# Pg6-Power_supply_1.net
KiCad netlist of a schematic drawn in Altium Designer
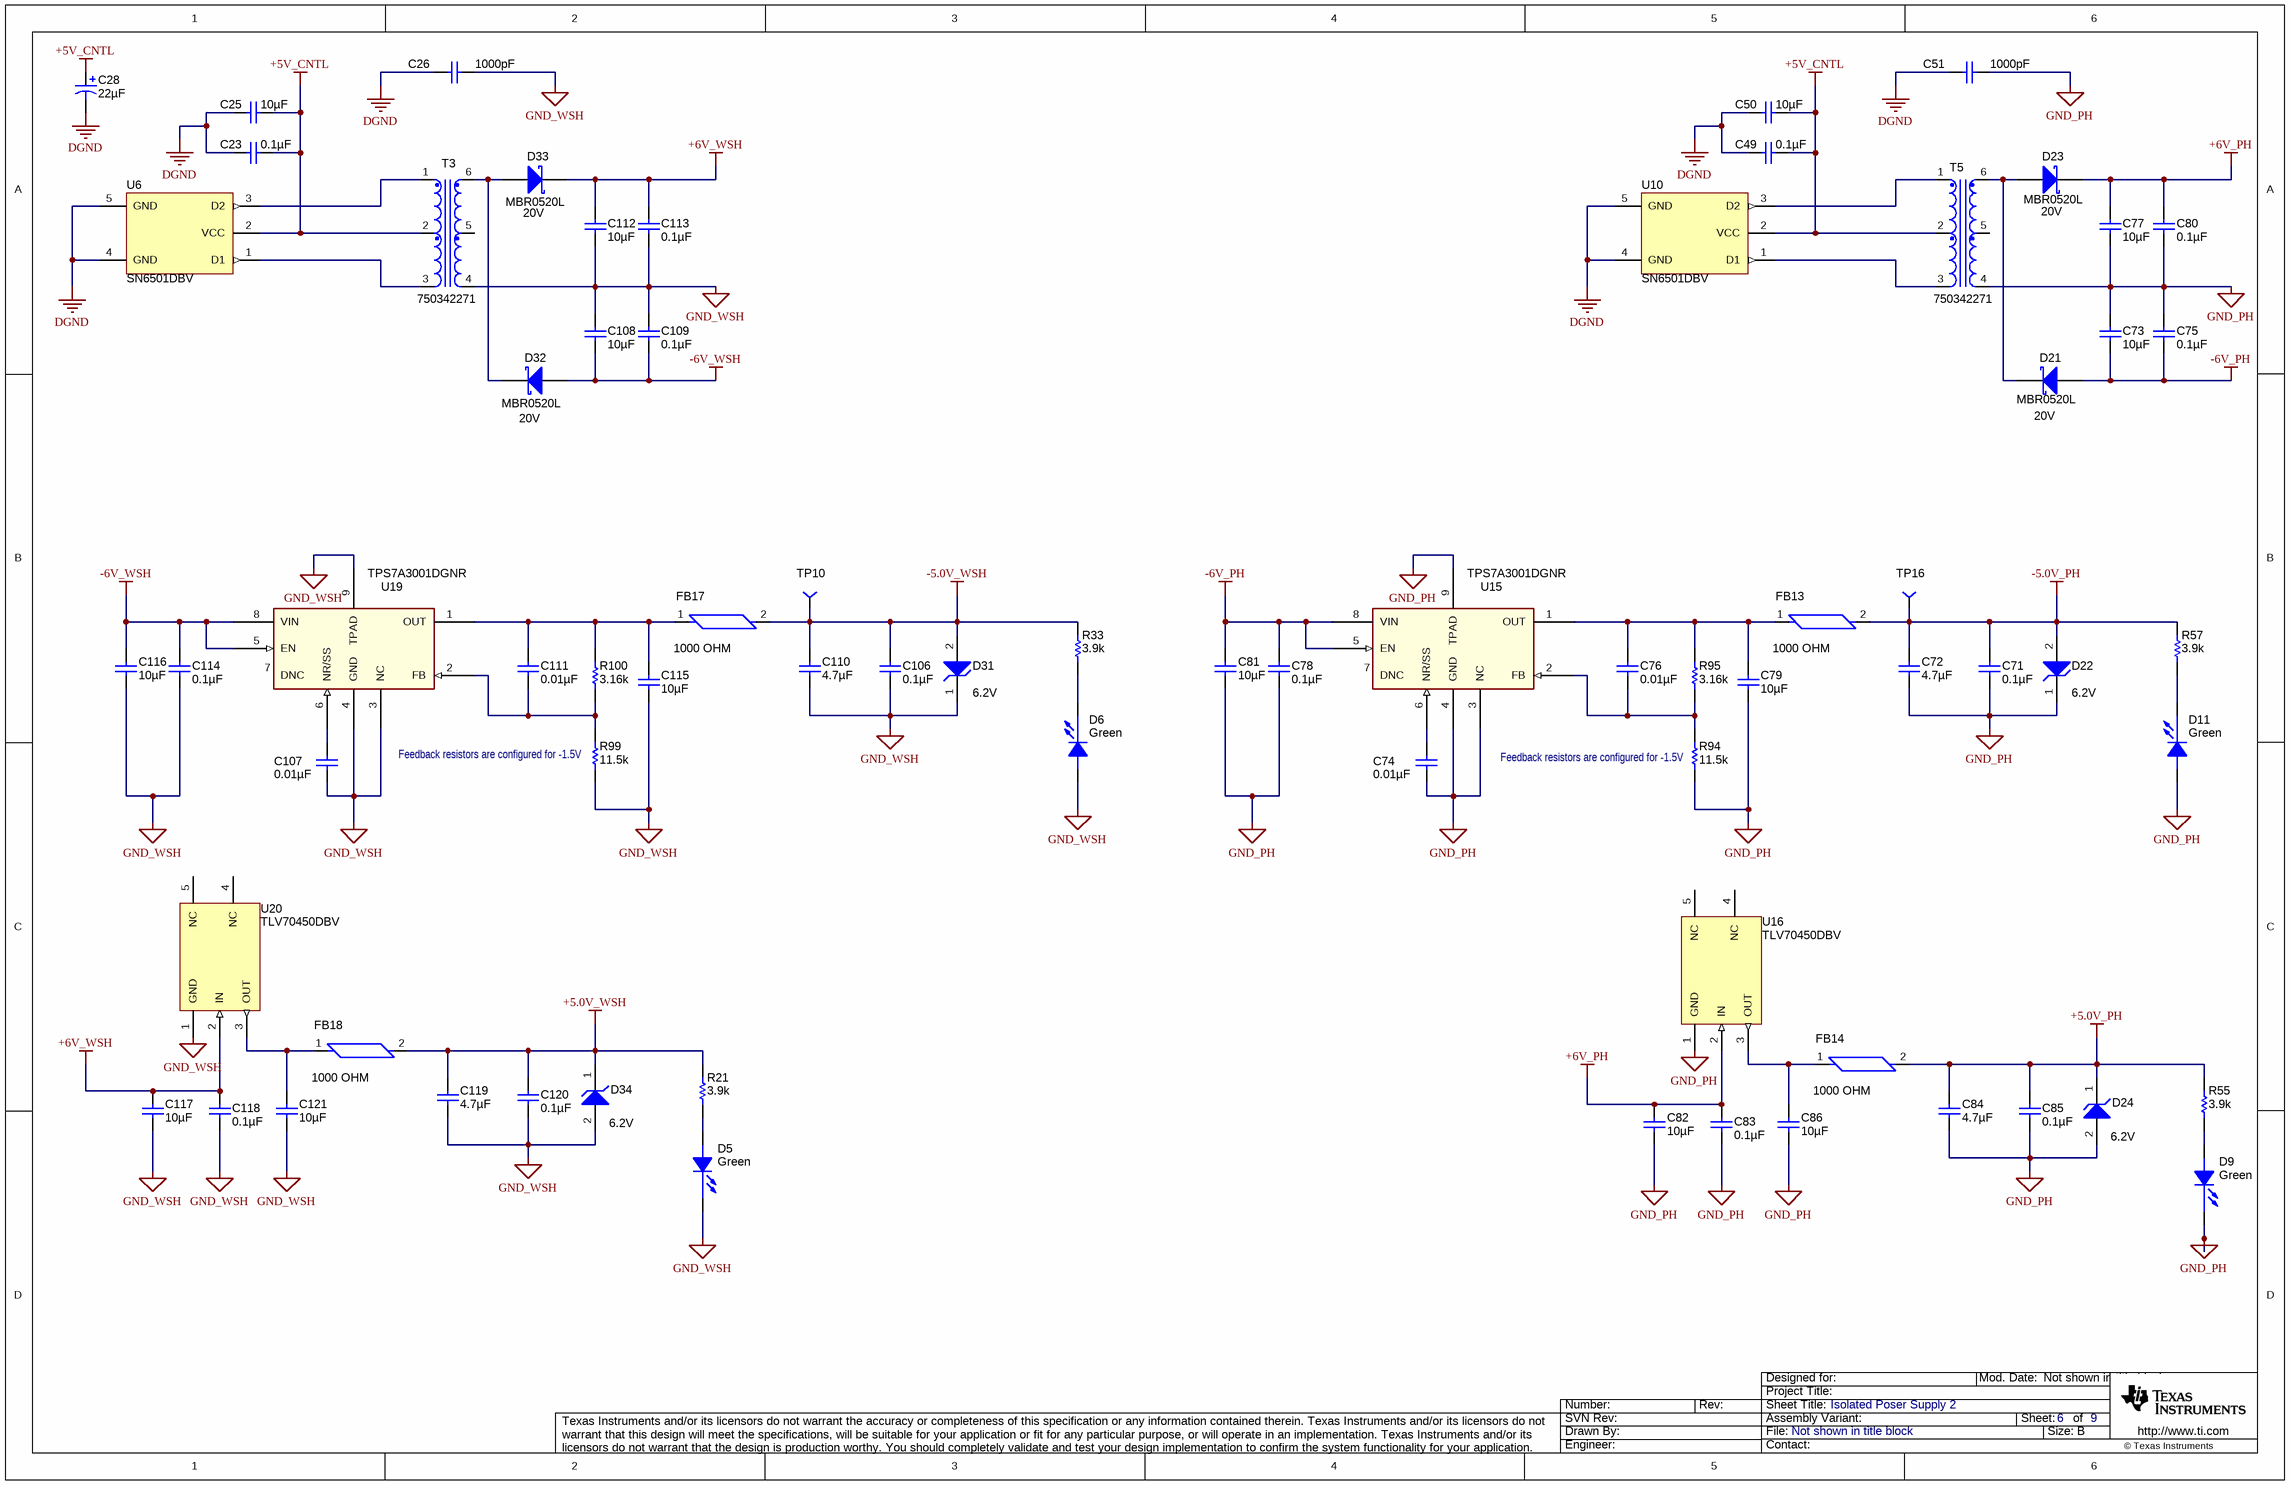
[diagram p0: Pg6-Power supply 1.SchDoc]

(export (version "E")
  (design (tool "Eeschema 10.0.6"))
  (components
    (comp (ref "C23")
      (value "~")
      (footprint "0603")
      (description "CAP, CERM, 0.1uF, 50V, +/-10%, X7R, 0603")
      (fields
        (field (name "PARTNUMBER") "C0603C104K5RACTU")
        (field (name "VALUEDISPLAYED") "0.1µF")
        (field (name "MANUFACTURER") "Kemet")
        (field (name "PUBLISHER") "Texas Instruments")
      )
      (libsource (lib "Capacitor_Ceramic") (part "C0603C104K5RACTU"))
    )
    (comp (ref "C25")
      (value "~")
      (footprint "1210")
      (description "CAP, CERM, 10uF, 35V, +/-20%, X7R, 1210")
      (fields
        (field (name "PARTNUMBER") "GMK325AB7106MM-T")
        (field (name "VALUEDISPLAYED") "10µF")
        (field (name "MANUFACTURER") "Taiyo Yuden")
        (field (name "PUBLISHER") "Texas Instruments")
      )
      (libsource (lib "Capacitor_Ceramic") (part "GMK325AB7106MM-T"))
    )
    (comp (ref "C26")
      (value "1000pF")
      (footprint "CAP_200mil")
      (description "CAP CER 1000PF 1KV 10% RADIAL")
      (fields
        (field (name "PARTNUMBER") "S102K29Y5PN63J5R")
        (field (name "MANUFACTURER") "Vishay BC Components")
        (field (name "PUBLISHER") "Texas Instruments")
      )
      (libsource (lib "TI-INDIA-ALTIUM") (part "202R18W102KV4E"))
    )
    (comp (ref "C28")
      (value "UUD1E220MCL1GS")
      (footprint "SM_RADIAL_5MM")
      (description "CAP, AL, 22uF, 25V, +/-20%, 0.76 ohm, SMD")
      (fields
        (field (name "VALUEDISPLAYED") "22µF")
        (field (name "MANUFACTURER") "Nichicon")
        (field (name "PUBLISHER") "Texas Instruments")
      )
      (libsource (lib "Capacitor_Aluminum") (part "UUD1E220MCL1GS"))
    )
    (comp (ref "C49")
      (value "~")
      (footprint "0603")
      (description "CAP, CERM, 0.1uF, 50V, +/-10%, X7R, 0603")
      (fields
        (field (name "PARTNUMBER") "C0603C104K5RACTU")
        (field (name "VALUEDISPLAYED") "0.1µF")
        (field (name "MANUFACTURER") "Kemet")
        (field (name "PUBLISHER") "Texas Instruments")
      )
      (libsource (lib "Capacitor_Ceramic") (part "C0603C104K5RACTU"))
    )
    (comp (ref "C50")
      (value "~")
      (footprint "1210")
      (description "CAP, CERM, 10uF, 35V, +/-20%, X7R, 1210")
      (fields
        (field (name "PARTNUMBER") "GMK325AB7106MM-T")
        (field (name "VALUEDISPLAYED") "10µF")
        (field (name "MANUFACTURER") "Taiyo Yuden")
        (field (name "PUBLISHER") "Texas Instruments")
      )
      (libsource (lib "Capacitor_Ceramic") (part "GMK325AB7106MM-T"))
    )
    (comp (ref "C51")
      (value "1000pF")
      (footprint "CAP_200mil")
      (description "CAP CER 1000PF 1KV 10% RADIAL")
      (fields
        (field (name "PARTNUMBER") "S102K29Y5PN63J5R")
        (field (name "MANUFACTURER") "Vishay BC Components")
        (field (name "PUBLISHER") "Texas Instruments")
      )
      (libsource (lib "TI-INDIA-ALTIUM") (part "202R18W102KV4E"))
    )
    (comp (ref "C71")
      (value "~")
      (footprint "0603")
      (description "CAP, CERM, 0.1uF, 50V, +/-10%, X7R, 0603")
      (fields
        (field (name "PARTNUMBER") "C0603C104K5RACTU")
        (field (name "VALUEDISPLAYED") "0.1µF")
        (field (name "MANUFACTURER") "Kemet")
        (field (name "PUBLISHER") "Texas Instruments")
      )
      (libsource (lib "Capacitor_Ceramic") (part "C0603C104K5RACTU"))
    )
    (comp (ref "C72")
      (value "~")
      (footprint "0805_HV")
      (description "CAP, CERM, 4.7uF, 50V, +/-10%, X5R, 0805")
      (fields
        (field (name "PARTNUMBER") "C2012X5R1H475K125AB")
        (field (name "VALUEDISPLAYED") "4.7µF")
        (field (name "MANUFACTURER") "TDK")
        (field (name "PUBLISHER") "Texas Instruments")
      )
      (libsource (lib "Capacitor_Ceramic") (part "C2012X5R1H475K125AB"))
    )
    (comp (ref "C73")
      (value "~")
      (footprint "1210")
      (description "CAP, CERM, 10uF, 35V, +/-20%, X7R, 1210")
      (fields
        (field (name "PARTNUMBER") "GMK325AB7106MM-T")
        (field (name "VALUEDISPLAYED") "10µF")
        (field (name "MANUFACTURER") "Taiyo Yuden")
        (field (name "PUBLISHER") "Texas Instruments")
      )
      (libsource (lib "Capacitor_Ceramic") (part "GMK325AB7106MM-T"))
    )
    (comp (ref "C74")
      (value "~")
      (footprint "0603")
      (description "CAP, CERM, 0.01uF, 100V, +/-5%, X7R, 0603")
      (fields
        (field (name "PARTNUMBER") "06031C103J4Z4A")
        (field (name "VALUEDISPLAYED") "0.01µF")
        (field (name "MANUFACTURER") "AVX")
        (field (name "PUBLISHER") "Texas Instruments")
      )
      (libsource (lib "Capacitor_Ceramic") (part "06031C103J4Z4A"))
    )
    (comp (ref "C75")
      (value "~")
      (footprint "0603")
      (description "CAP, CERM, 0.1uF, 50V, +/-10%, X7R, 0603")
      (fields
        (field (name "PARTNUMBER") "C0603C104K5RACTU")
        (field (name "VALUEDISPLAYED") "0.1µF")
        (field (name "MANUFACTURER") "Kemet")
        (field (name "PUBLISHER") "Texas Instruments")
      )
      (libsource (lib "Capacitor_Ceramic") (part "C0603C104K5RACTU"))
    )
    (comp (ref "C76")
      (value "~")
      (footprint "0603")
      (description "CAP, CERM, 0.01uF, 100V, +/-5%, X7R, 0603")
      (fields
        (field (name "PARTNUMBER") "06031C103J4Z4A")
        (field (name "VALUEDISPLAYED") "0.01µF")
        (field (name "MANUFACTURER") "AVX")
        (field (name "PUBLISHER") "Texas Instruments")
      )
      (libsource (lib "Capacitor_Ceramic") (part "06031C103J4Z4A"))
    )
    (comp (ref "C77")
      (value "~")
      (footprint "1210")
      (description "CAP, CERM, 10uF, 35V, +/-20%, X7R, 1210")
      (fields
        (field (name "PARTNUMBER") "GMK325AB7106MM-T")
        (field (name "VALUEDISPLAYED") "10µF")
        (field (name "MANUFACTURER") "Taiyo Yuden")
        (field (name "PUBLISHER") "Texas Instruments")
      )
      (libsource (lib "Capacitor_Ceramic") (part "GMK325AB7106MM-T"))
    )
    (comp (ref "C78")
      (value "~")
      (footprint "0603")
      (description "CAP, CERM, 0.1uF, 50V, +/-10%, X7R, 0603")
      (fields
        (field (name "PARTNUMBER") "C0603C104K5RACTU")
        (field (name "VALUEDISPLAYED") "0.1µF")
        (field (name "MANUFACTURER") "Kemet")
        (field (name "PUBLISHER") "Texas Instruments")
      )
      (libsource (lib "Capacitor_Ceramic") (part "C0603C104K5RACTU"))
    )
    (comp (ref "C79")
      (value "~")
      (footprint "1210")
      (description "CAP, CERM, 10uF, 35V, +/-20%, X7R, 1210")
      (fields
        (field (name "PARTNUMBER") "GMK325AB7106MM-T")
        (field (name "VALUEDISPLAYED") "10µF")
        (field (name "MANUFACTURER") "Taiyo Yuden")
        (field (name "PUBLISHER") "Texas Instruments")
      )
      (libsource (lib "Capacitor_Ceramic") (part "GMK325AB7106MM-T"))
    )
    (comp (ref "C80")
      (value "~")
      (footprint "0603")
      (description "CAP, CERM, 0.1uF, 50V, +/-10%, X7R, 0603")
      (fields
        (field (name "PARTNUMBER") "C0603C104K5RACTU")
        (field (name "VALUEDISPLAYED") "0.1µF")
        (field (name "MANUFACTURER") "Kemet")
        (field (name "PUBLISHER") "Texas Instruments")
      )
      (libsource (lib "Capacitor_Ceramic") (part "C0603C104K5RACTU"))
    )
    (comp (ref "C81")
      (value "~")
      (footprint "1210")
      (description "CAP, CERM, 10uF, 35V, +/-20%, X7R, 1210")
      (fields
        (field (name "PARTNUMBER") "GMK325AB7106MM-T")
        (field (name "VALUEDISPLAYED") "10µF")
        (field (name "MANUFACTURER") "Taiyo Yuden")
        (field (name "PUBLISHER") "Texas Instruments")
      )
      (libsource (lib "Capacitor_Ceramic") (part "GMK325AB7106MM-T"))
    )
    (comp (ref "C82")
      (value "~")
      (footprint "1210")
      (description "CAP, CERM, 10uF, 35V, +/-20%, X7R, 1210")
      (fields
        (field (name "PARTNUMBER") "GMK325AB7106MM-T")
        (field (name "VALUEDISPLAYED") "10µF")
        (field (name "MANUFACTURER") "Taiyo Yuden")
        (field (name "PUBLISHER") "Texas Instruments")
      )
      (libsource (lib "Capacitor_Ceramic") (part "GMK325AB7106MM-T"))
    )
    (comp (ref "C83")
      (value "~")
      (footprint "0603")
      (description "CAP, CERM, 0.1uF, 50V, +/-10%, X7R, 0603")
      (fields
        (field (name "PARTNUMBER") "C0603C104K5RACTU")
        (field (name "VALUEDISPLAYED") "0.1µF")
        (field (name "MANUFACTURER") "Kemet")
        (field (name "PUBLISHER") "Texas Instruments")
      )
      (libsource (lib "Capacitor_Ceramic") (part "C0603C104K5RACTU"))
    )
    (comp (ref "C84")
      (value "~")
      (footprint "0805_HV")
      (description "CAP, CERM, 4.7uF, 50V, +/-10%, X5R, 0805")
      (fields
        (field (name "PARTNUMBER") "C2012X5R1H475K125AB")
        (field (name "VALUEDISPLAYED") "4.7µF")
        (field (name "MANUFACTURER") "TDK")
        (field (name "PUBLISHER") "Texas Instruments")
      )
      (libsource (lib "Capacitor_Ceramic") (part "C2012X5R1H475K125AB"))
    )
    (comp (ref "C85")
      (value "~")
      (footprint "0603")
      (description "CAP, CERM, 0.1uF, 50V, +/-10%, X7R, 0603")
      (fields
        (field (name "PARTNUMBER") "C0603C104K5RACTU")
        (field (name "VALUEDISPLAYED") "0.1µF")
        (field (name "MANUFACTURER") "Kemet")
        (field (name "PUBLISHER") "Texas Instruments")
      )
      (libsource (lib "Capacitor_Ceramic") (part "C0603C104K5RACTU"))
    )
    (comp (ref "C86")
      (value "~")
      (footprint "1210")
      (description "CAP, CERM, 10uF, 35V, +/-20%, X7R, 1210")
      (fields
        (field (name "PARTNUMBER") "GMK325AB7106MM-T")
        (field (name "VALUEDISPLAYED") "10µF")
        (field (name "MANUFACTURER") "Taiyo Yuden")
        (field (name "PUBLISHER") "Texas Instruments")
      )
      (libsource (lib "Capacitor_Ceramic") (part "GMK325AB7106MM-T"))
    )
    (comp (ref "C106")
      (value "~")
      (footprint "0603")
      (description "CAP, CERM, 0.1uF, 50V, +/-10%, X7R, 0603")
      (fields
        (field (name "PARTNUMBER") "C0603C104K5RACTU")
        (field (name "VALUEDISPLAYED") "0.1µF")
        (field (name "MANUFACTURER") "Kemet")
        (field (name "PUBLISHER") "Texas Instruments")
      )
      (libsource (lib "Capacitor_Ceramic") (part "C0603C104K5RACTU"))
    )
    (comp (ref "C107")
      (value "~")
      (footprint "0603")
      (description "CAP, CERM, 0.01uF, 100V, +/-5%, X7R, 0603")
      (fields
        (field (name "PARTNUMBER") "06031C103J4Z4A")
        (field (name "VALUEDISPLAYED") "0.01µF")
        (field (name "MANUFACTURER") "AVX")
        (field (name "PUBLISHER") "Texas Instruments")
      )
      (libsource (lib "Capacitor_Ceramic") (part "06031C103J4Z4A"))
    )
    (comp (ref "C108")
      (value "~")
      (footprint "1210")
      (description "CAP, CERM, 10uF, 35V, +/-20%, X7R, 1210")
      (fields
        (field (name "PARTNUMBER") "GMK325AB7106MM-T")
        (field (name "VALUEDISPLAYED") "10µF")
        (field (name "MANUFACTURER") "Taiyo Yuden")
        (field (name "PUBLISHER") "Texas Instruments")
      )
      (libsource (lib "Capacitor_Ceramic") (part "GMK325AB7106MM-T"))
    )
    (comp (ref "C109")
      (value "~")
      (footprint "0603")
      (description "CAP, CERM, 0.1uF, 50V, +/-10%, X7R, 0603")
      (fields
        (field (name "PARTNUMBER") "C0603C104K5RACTU")
        (field (name "VALUEDISPLAYED") "0.1µF")
        (field (name "MANUFACTURER") "Kemet")
        (field (name "PUBLISHER") "Texas Instruments")
      )
      (libsource (lib "Capacitor_Ceramic") (part "C0603C104K5RACTU"))
    )
    (comp (ref "C110")
      (value "~")
      (footprint "0805_HV")
      (description "CAP, CERM, 4.7uF, 50V, +/-10%, X5R, 0805")
      (fields
        (field (name "PARTNUMBER") "C2012X5R1H475K125AB")
        (field (name "VALUEDISPLAYED") "4.7µF")
        (field (name "MANUFACTURER") "TDK")
        (field (name "PUBLISHER") "Texas Instruments")
      )
      (libsource (lib "Capacitor_Ceramic") (part "C2012X5R1H475K125AB"))
    )
    (comp (ref "C111")
      (value "~")
      (footprint "0603")
      (description "CAP, CERM, 0.01uF, 100V, +/-5%, X7R, 0603")
      (fields
        (field (name "PARTNUMBER") "06031C103J4Z4A")
        (field (name "VALUEDISPLAYED") "0.01µF")
        (field (name "MANUFACTURER") "AVX")
        (field (name "PUBLISHER") "Texas Instruments")
      )
      (libsource (lib "Capacitor_Ceramic") (part "06031C103J4Z4A"))
    )
    (comp (ref "C112")
      (value "~")
      (footprint "1210")
      (description "CAP, CERM, 10uF, 35V, +/-20%, X7R, 1210")
      (fields
        (field (name "PARTNUMBER") "GMK325AB7106MM-T")
        (field (name "VALUEDISPLAYED") "10µF")
        (field (name "MANUFACTURER") "Taiyo Yuden")
        (field (name "PUBLISHER") "Texas Instruments")
      )
      (libsource (lib "Capacitor_Ceramic") (part "GMK325AB7106MM-T"))
    )
    (comp (ref "C113")
      (value "~")
      (footprint "0603")
      (description "CAP, CERM, 0.1uF, 50V, +/-10%, X7R, 0603")
      (fields
        (field (name "PARTNUMBER") "C0603C104K5RACTU")
        (field (name "VALUEDISPLAYED") "0.1µF")
        (field (name "MANUFACTURER") "Kemet")
        (field (name "PUBLISHER") "Texas Instruments")
      )
      (libsource (lib "Capacitor_Ceramic") (part "C0603C104K5RACTU"))
    )
    (comp (ref "C114")
      (value "~")
      (footprint "0603")
      (description "CAP, CERM, 0.1uF, 50V, +/-10%, X7R, 0603")
      (fields
        (field (name "PARTNUMBER") "C0603C104K5RACTU")
        (field (name "VALUEDISPLAYED") "0.1µF")
        (field (name "MANUFACTURER") "Kemet")
        (field (name "PUBLISHER") "Texas Instruments")
      )
      (libsource (lib "Capacitor_Ceramic") (part "C0603C104K5RACTU"))
    )
    (comp (ref "C115")
      (value "~")
      (footprint "1210")
      (description "CAP, CERM, 10uF, 35V, +/-20%, X7R, 1210")
      (fields
        (field (name "PARTNUMBER") "GMK325AB7106MM-T")
        (field (name "VALUEDISPLAYED") "10µF")
        (field (name "MANUFACTURER") "Taiyo Yuden")
        (field (name "PUBLISHER") "Texas Instruments")
      )
      (libsource (lib "Capacitor_Ceramic") (part "GMK325AB7106MM-T"))
    )
    (comp (ref "C116")
      (value "~")
      (footprint "1210")
      (description "CAP, CERM, 10uF, 35V, +/-20%, X7R, 1210")
      (fields
        (field (name "PARTNUMBER") "GMK325AB7106MM-T")
        (field (name "VALUEDISPLAYED") "10µF")
        (field (name "MANUFACTURER") "Taiyo Yuden")
        (field (name "PUBLISHER") "Texas Instruments")
      )
      (libsource (lib "Capacitor_Ceramic") (part "GMK325AB7106MM-T"))
    )
    (comp (ref "C117")
      (value "~")
      (footprint "1210")
      (description "CAP, CERM, 10uF, 35V, +/-20%, X7R, 1210")
      (fields
        (field (name "PARTNUMBER") "GMK325AB7106MM-T")
        (field (name "VALUEDISPLAYED") "10µF")
        (field (name "MANUFACTURER") "Taiyo Yuden")
        (field (name "PUBLISHER") "Texas Instruments")
      )
      (libsource (lib "Capacitor_Ceramic") (part "GMK325AB7106MM-T"))
    )
    (comp (ref "C118")
      (value "~")
      (footprint "0603")
      (description "CAP, CERM, 0.1uF, 50V, +/-10%, X7R, 0603")
      (fields
        (field (name "PARTNUMBER") "C0603C104K5RACTU")
        (field (name "VALUEDISPLAYED") "0.1µF")
        (field (name "MANUFACTURER") "Kemet")
        (field (name "PUBLISHER") "Texas Instruments")
      )
      (libsource (lib "Capacitor_Ceramic") (part "C0603C104K5RACTU"))
    )
    (comp (ref "C119")
      (value "~")
      (footprint "0805_HV")
      (description "CAP, CERM, 4.7uF, 50V, +/-10%, X5R, 0805")
      (fields
        (field (name "PARTNUMBER") "C2012X5R1H475K125AB")
        (field (name "VALUEDISPLAYED") "4.7µF")
        (field (name "MANUFACTURER") "TDK")
        (field (name "PUBLISHER") "Texas Instruments")
      )
      (libsource (lib "Capacitor_Ceramic") (part "C2012X5R1H475K125AB"))
    )
    (comp (ref "C120")
      (value "~")
      (footprint "0603")
      (description "CAP, CERM, 0.1uF, 50V, +/-10%, X7R, 0603")
      (fields
        (field (name "PARTNUMBER") "C0603C104K5RACTU")
        (field (name "VALUEDISPLAYED") "0.1µF")
        (field (name "MANUFACTURER") "Kemet")
        (field (name "PUBLISHER") "Texas Instruments")
      )
      (libsource (lib "Capacitor_Ceramic") (part "C0603C104K5RACTU"))
    )
    (comp (ref "C121")
      (value "~")
      (footprint "1210")
      (description "CAP, CERM, 10uF, 35V, +/-20%, X7R, 1210")
      (fields
        (field (name "PARTNUMBER") "GMK325AB7106MM-T")
        (field (name "VALUEDISPLAYED") "10µF")
        (field (name "MANUFACTURER") "Taiyo Yuden")
        (field (name "PUBLISHER") "Texas Instruments")
      )
      (libsource (lib "Capacitor_Ceramic") (part "GMK325AB7106MM-T"))
    )
    (comp (ref "D5")
      (value "Green")
      (footprint "LED0603AA")
      (description "LED SmartLED Green 570NM")
      (fields
        (field (name "PARTNUMBER") "LG L29K-G2J1-24-Z")
        (field (name "MANUFACTURER") "OSRAM")
        (field (name "PUBLISHER") "TI")
        (field (name "SYMBOLCREATOR") "x0120606")
      )
      (libsource (lib "TI-INDIA-ALTIUM") (part "LED_LG L29K-G2J1-24-Z"))
    )
    (comp (ref "D6")
      (value "Green")
      (footprint "LED0603AA")
      (description "LED SmartLED Green 570NM")
      (fields
        (field (name "PARTNUMBER") "LG L29K-G2J1-24-Z")
        (field (name "MANUFACTURER") "OSRAM")
        (field (name "PUBLISHER") "TI")
        (field (name "SYMBOLCREATOR") "x0120606")
      )
      (libsource (lib "TI-INDIA-ALTIUM") (part "LED_LG L29K-G2J1-24-Z"))
    )
    (comp (ref "D9")
      (value "Green")
      (footprint "LED0603AA")
      (description "LED SmartLED Green 570NM")
      (fields
        (field (name "PARTNUMBER") "LG L29K-G2J1-24-Z")
        (field (name "MANUFACTURER") "OSRAM")
        (field (name "PUBLISHER") "TI")
        (field (name "SYMBOLCREATOR") "x0120606")
      )
      (libsource (lib "TI-INDIA-ALTIUM") (part "LED_LG L29K-G2J1-24-Z"))
    )
    (comp (ref "D11")
      (value "Green")
      (footprint "LED0603AA")
      (description "LED SmartLED Green 570NM")
      (fields
        (field (name "PARTNUMBER") "LG L29K-G2J1-24-Z")
        (field (name "MANUFACTURER") "OSRAM")
        (field (name "PUBLISHER") "TI")
        (field (name "SYMBOLCREATOR") "x0120606")
      )
      (libsource (lib "TI-INDIA-ALTIUM") (part "LED_LG L29K-G2J1-24-Z"))
    )
    (comp (ref "D21")
      (value "MBR0520L")
      (footprint "SOD-123")
      (description "Diode, Schottky, 20V, 0.5A, SOD-123")
      (fields
        (field (name "ALTIUM_VALUE") "20V")
        (field (name "MANUFACTURER") "Fairchild Semiconductor")
        (field (name "PUBLISHER") "Texas Instruments")
      )
      (libsource (lib "Diode") (part "MBR0520LT1G"))
    )
    (comp (ref "D22")
      (value "6.2V")
      (footprint "powerDI123")
      (description "Diode, Zener, 6.2V, 1W, PowerDI123")
      (fields
        (field (name "PARTNUMBER") "DFLZ6V2-7")
        (field (name "MANUFACTURER") "Diodes Inc.")
        (field (name "PUBLISHER") "Texas Instruments")
      )
      (libsource (lib "ZenerDiodes") (part "DFLZ6V2-7"))
    )
    (comp (ref "D23")
      (value "MBR0520L")
      (footprint "SOD-123")
      (description "Diode, Schottky, 20V, 0.5A, SOD-123")
      (fields
        (field (name "ALTIUM_VALUE") "20V")
        (field (name "MANUFACTURER") "Fairchild Semiconductor")
        (field (name "PUBLISHER") "Texas Instruments")
      )
      (libsource (lib "Diode") (part "MBR0520LT1G"))
    )
    (comp (ref "D24")
      (value "6.2V")
      (footprint "powerDI123")
      (description "Diode, Zener, 6.2V, 1W, PowerDI123")
      (fields
        (field (name "PARTNUMBER") "DFLZ6V2-7")
        (field (name "MANUFACTURER") "Diodes Inc.")
        (field (name "PUBLISHER") "Texas Instruments")
      )
      (libsource (lib "ZenerDiodes") (part "DFLZ6V2-7"))
    )
    (comp (ref "D31")
      (value "6.2V")
      (footprint "powerDI123")
      (description "Diode, Zener, 6.2V, 1W, PowerDI123")
      (fields
        (field (name "PARTNUMBER") "DFLZ6V2-7")
        (field (name "MANUFACTURER") "Diodes Inc.")
        (field (name "PUBLISHER") "Texas Instruments")
      )
      (libsource (lib "ZenerDiodes") (part "DFLZ6V2-7"))
    )
    (comp (ref "D32")
      (value "MBR0520L")
      (footprint "SOD-123")
      (description "Diode, Schottky, 20V, 0.5A, SOD-123")
      (fields
        (field (name "ALTIUM_VALUE") "20V")
        (field (name "MANUFACTURER") "Fairchild Semiconductor")
        (field (name "PUBLISHER") "Texas Instruments")
      )
      (libsource (lib "Diode") (part "MBR0520LT1G"))
    )
    (comp (ref "D33")
      (value "MBR0520L")
      (footprint "SOD-123")
      (description "Diode, Schottky, 20V, 0.5A, SOD-123")
      (fields
        (field (name "ALTIUM_VALUE") "20V")
        (field (name "MANUFACTURER") "Fairchild Semiconductor")
        (field (name "PUBLISHER") "Texas Instruments")
      )
      (libsource (lib "Diode") (part "MBR0520LT1G"))
    )
    (comp (ref "D34")
      (value "6.2V")
      (footprint "powerDI123")
      (description "Diode, Zener, 6.2V, 1W, PowerDI123")
      (fields
        (field (name "PARTNUMBER") "DFLZ6V2-7")
        (field (name "MANUFACTURER") "Diodes Inc.")
        (field (name "PUBLISHER") "Texas Instruments")
      )
      (libsource (lib "ZenerDiodes") (part "DFLZ6V2-7"))
    )
    (comp (ref "FB13")
      (value "1000 OHM")
      (footprint "FB0603")
      (description "FERRITE CHIP 1000 OHM 300MA 0603")
      (fields
        (field (name "PARTNUMBER") "MMZ1608B102C")
        (field (name "MANUFACTURER") "TDK Corporation")
        (field (name "PUBLISHER") "TI")
      )
      (libsource (lib "TI-INDIA-ALTIUM") (part "MMZ1608B102C"))
    )
    (comp (ref "FB14")
      (value "1000 OHM")
      (footprint "FB0603")
      (description "FERRITE CHIP 1000 OHM 300MA 0603")
      (fields
        (field (name "PARTNUMBER") "MMZ1608B102C")
        (field (name "MANUFACTURER") "TDK Corporation")
        (field (name "PUBLISHER") "TI")
      )
      (libsource (lib "TI-INDIA-ALTIUM") (part "MMZ1608B102C"))
    )
    (comp (ref "FB17")
      (value "1000 OHM")
      (footprint "FB0603")
      (description "FERRITE CHIP 1000 OHM 300MA 0603")
      (fields
        (field (name "PARTNUMBER") "MMZ1608B102C")
        (field (name "MANUFACTURER") "TDK Corporation")
        (field (name "PUBLISHER") "TI")
      )
      (libsource (lib "TI-INDIA-ALTIUM") (part "MMZ1608B102C"))
    )
    (comp (ref "FB18")
      (value "1000 OHM")
      (footprint "FB0603")
      (description "FERRITE CHIP 1000 OHM 300MA 0603")
      (fields
        (field (name "PARTNUMBER") "MMZ1608B102C")
        (field (name "MANUFACTURER") "TDK Corporation")
        (field (name "PUBLISHER") "TI")
      )
      (libsource (lib "TI-INDIA-ALTIUM") (part "MMZ1608B102C"))
    )
    (comp (ref "R21")
      (value "3.9k")
      (footprint "0603")
      (description "RES, 3.9k ohm, 5%, 0.1W, 0603")
      (fields
        (field (name "PARTNUMBER") "CRCW06033K90JNEA")
        (field (name "MANUFACTURER") "Vishay-Dale")
        (field (name "PUBLISHER") "Texas Instruments")
      )
      (libsource (lib "Resistor_0603") (part "CRCW06033K90JNEA"))
    )
    (comp (ref "R33")
      (value "3.9k")
      (footprint "0603")
      (description "RES, 3.9k ohm, 5%, 0.1W, 0603")
      (fields
        (field (name "PARTNUMBER") "CRCW06033K90JNEA")
        (field (name "MANUFACTURER") "Vishay-Dale")
        (field (name "PUBLISHER") "Texas Instruments")
      )
      (libsource (lib "Resistor_0603") (part "CRCW06033K90JNEA"))
    )
    (comp (ref "R55")
      (value "3.9k")
      (footprint "0603")
      (description "RES, 3.9k ohm, 5%, 0.1W, 0603")
      (fields
        (field (name "PARTNUMBER") "CRCW06033K90JNEA")
        (field (name "MANUFACTURER") "Vishay-Dale")
        (field (name "PUBLISHER") "Texas Instruments")
      )
      (libsource (lib "Resistor_0603") (part "CRCW06033K90JNEA"))
    )
    (comp (ref "R57")
      (value "3.9k")
      (footprint "0603")
      (description "RES, 3.9k ohm, 5%, 0.1W, 0603")
      (fields
        (field (name "PARTNUMBER") "CRCW06033K90JNEA")
        (field (name "MANUFACTURER") "Vishay-Dale")
        (field (name "PUBLISHER") "Texas Instruments")
      )
      (libsource (lib "Resistor_0603") (part "CRCW06033K90JNEA"))
    )
    (comp (ref "R94")
      (value "11.5k")
      (footprint "0603")
      (description "RES, 11.5k ohm, 1%, 0.1W, 0603")
      (fields
        (field (name "PARTNUMBER") "CRCW060311K5FKEA")
        (field (name "MANUFACTURER") "Vishay-Dale")
        (field (name "PUBLISHER") "Texas Instruments")
      )
      (libsource (lib "Resistor_0603") (part "CRCW060311K5FKEA"))
    )
    (comp (ref "R95")
      (value "RC0603FR-073K16L")
      (footprint "0603")
      (description "RES, 3.16 k, 1%, 0.1 W, 0603")
      (fields
        (field (name "VALUEDISPLAYED") "3.16k")
        (field (name "MANUFACTURER") "Yageo America")
        (field (name "PUBLISHER") "Texas Instruments")
      )
      (libsource (lib "Resistor_0603") (part "RC0603FR-073K16L"))
    )
    (comp (ref "R99")
      (value "11.5k")
      (footprint "0603")
      (description "RES, 11.5k ohm, 1%, 0.1W, 0603")
      (fields
        (field (name "PARTNUMBER") "CRCW060311K5FKEA")
        (field (name "MANUFACTURER") "Vishay-Dale")
        (field (name "PUBLISHER") "Texas Instruments")
      )
      (libsource (lib "Resistor_0603") (part "CRCW060311K5FKEA"))
    )
    (comp (ref "R100")
      (value "RC0603FR-073K16L")
      (footprint "0603")
      (description "RES, 3.16 k, 1%, 0.1 W, 0603")
      (fields
        (field (name "VALUEDISPLAYED") "3.16k")
        (field (name "MANUFACTURER") "Yageo America")
        (field (name "PUBLISHER") "Texas Instruments")
      )
      (libsource (lib "Resistor_0603") (part "RC0603FR-073K16L"))
    )
    (comp (ref "T3")
      (value "750342271")
      (footprint "760390015")
      (description "Transformer 469uH SMD")
      (fields (field (name "MANUFACTURER") "Wurth Electronics Midcom") (field (name "PUBLISHER") "TI"))
      (libsource (lib "Isolated current sensing") (part "TRNSFMR"))
    )
    (comp (ref "T5")
      (value "750342271")
      (footprint "760390015")
      (description "Transformer 469uH SMD")
      (fields (field (name "MANUFACTURER") "Wurth Electronics Midcom") (field (name "PUBLISHER") "TI"))
      (libsource (lib "Isolated current sensing") (part "TRNSFMR"))
    )
    (comp (ref "TP10")
      (value "~")
      (footprint "TP-040_RND")
      (description "Test Point, O.040 Hole")
      (fields (field (name "MANUFACTURER") "STD"))
      (libsource (lib "PADSlegacy_Hardware") (part "TP-040_RND"))
    )
    (comp (ref "TP16")
      (value "~")
      (footprint "TP-040_RND")
      (description "Test Point, O.040 Hole")
      (fields (field (name "MANUFACTURER") "STD"))
      (libsource (lib "PADSlegacy_Hardware") (part "TP-040_RND"))
    )
    (comp (ref "U6")
      (value "SN6501DBV")
      (footprint "DBV0005A_N")
      (description "Transformer Driver for Isolated Power Supplies, DBV0005A")
      (fields
        (field (name "MANUFACTURER") "Texas Instruments")
        (field (name "SYMBOLCREATOR") "a0411947")
        (field (name "PUBLISHER") "Texas Instruments")
      )
      (libsource (lib "TI_Pre_Release") (part "SN6501DBV"))
    )
    (comp (ref "U10")
      (value "SN6501DBV")
      (footprint "DBV0005A_N")
      (description "Transformer Driver for Isolated Power Supplies, DBV0005A")
      (fields
        (field (name "MANUFACTURER") "Texas Instruments")
        (field (name "SYMBOLCREATOR") "a0411947")
        (field (name "PUBLISHER") "Texas Instruments")
      )
      (libsource (lib "TI_Pre_Release") (part "SN6501DBV"))
    )
    (comp (ref "U15")
      (value "~")
      (footprint "MSOP8(DGN)")
      (description "-36V, -200mA, Ultralow-Noise, Negative Linear Regulator")
      (fields
        (field (name "MANUFACTURER") "Texas Instruments")
        (field (name "PARTNUMBER") "TPS7A3001DGNR")
        (field (name "PUBLISHER") "Texas Instruments")
        (field (name "SYMBOLCREATOR") "x0120606")
      )
      (libsource (lib "TI-INDIA-ALTIUM") (part "TPS7A3001DGNR"))
    )
    (comp (ref "U16")
      (value "TLV70450DBV")
      (footprint "DBV0005A_N")
      (description "Regulator, LDO, 5V, 0.15A, SOT23-5")
      (fields
        (field (name "MANUFACTURER") "Texas Instruments")
        (field (name "SYMBOLCREATOR") "x0120606")
        (field (name "PUBLISHER") "Texas Instruments")
      )
      (libsource (lib "TI-INDIA-ALTIUM") (part "TLV70450DBV"))
    )
    (comp (ref "U19")
      (value "~")
      (footprint "MSOP8(DGN)")
      (description "-36V, -200mA, Ultralow-Noise, Negative Linear Regulator")
      (fields
        (field (name "MANUFACTURER") "Texas Instruments")
        (field (name "PARTNUMBER") "TPS7A3001DGNR")
        (field (name "PUBLISHER") "Texas Instruments")
        (field (name "SYMBOLCREATOR") "x0120606")
      )
      (libsource (lib "TI-INDIA-ALTIUM") (part "TPS7A3001DGNR"))
    )
    (comp (ref "U20")
      (value "TLV70450DBV")
      (footprint "DBV0005A_N")
      (description "Regulator, LDO, 5V, 0.15A, SOT23-5")
      (fields
        (field (name "MANUFACTURER") "Texas Instruments")
        (field (name "SYMBOLCREATOR") "x0120606")
        (field (name "PUBLISHER") "Texas Instruments")
      )
      (libsource (lib "TI-INDIA-ALTIUM") (part "TLV70450DBV"))
    )
  )
  (nets
    (net (code "1") (name "+5.0V_PH") (class "Default")
      (node (ref "C84") (pin "2") (pinfunction "2_2") (pintype "passive"))
      (node (ref "C85") (pin "1") (pinfunction "1_1") (pintype "passive"))
      (node (ref "D24") (pin "1") (pinfunction "K_1") (pintype "passive"))
      (node (ref "FB14") (pin "2") (pinfunction "2_2") (pintype "passive"))
      (node (ref "R55") (pin "2") (pinfunction "2_2") (pintype "passive"))
    )
    (net (code "2") (name "+5.0V_WSH") (class "Default")
      (node (ref "C119") (pin "2") (pinfunction "2_2") (pintype "passive"))
      (node (ref "C120") (pin "1") (pinfunction "1_1") (pintype "passive"))
      (node (ref "D34") (pin "1") (pinfunction "K_1") (pintype "passive"))
      (node (ref "FB18") (pin "2") (pinfunction "2_2") (pintype "passive"))
      (node (ref "R21") (pin "2") (pinfunction "2_2") (pintype "passive"))
    )
    (net (code "3") (name "+5V_CNTL") (class "Default")
      (node (ref "C23") (pin "2") (pinfunction "2_2") (pintype "passive"))
      (node (ref "C25") (pin "2") (pinfunction "2_2") (pintype "passive"))
      (node (ref "C28") (pin "1") (pinfunction "+_1") (pintype "passive"))
      (node (ref "C49") (pin "2") (pinfunction "2_2") (pintype "passive"))
      (node (ref "C50") (pin "2") (pinfunction "2_2") (pintype "passive"))
      (node (ref "T3") (pin "2") (pinfunction "2_2") (pintype "passive"))
      (node (ref "T5") (pin "2") (pinfunction "2_2") (pintype "passive"))
      (node (ref "U10") (pin "2") (pinfunction "VCC_2") (pintype "power_in"))
      (node (ref "U6") (pin "2") (pinfunction "VCC_2") (pintype "power_in"))
    )
    (net (code "4") (name "+6V_PH") (class "Default")
      (node (ref "C77") (pin "1") (pinfunction "1_1") (pintype "passive"))
      (node (ref "C80") (pin "1") (pinfunction "1_1") (pintype "passive"))
      (node (ref "C82") (pin "2") (pinfunction "2_2") (pintype "passive"))
      (node (ref "C83") (pin "1") (pinfunction "1_1") (pintype "passive"))
      (node (ref "D23") (pin "1") (pinfunction "K_1") (pintype "passive"))
      (node (ref "U16") (pin "2") (pinfunction "IN_2") (pintype "input"))
    )
    (net (code "5") (name "+6V_WSH") (class "Default")
      (node (ref "C112") (pin "1") (pinfunction "1_1") (pintype "passive"))
      (node (ref "C113") (pin "1") (pinfunction "1_1") (pintype "passive"))
      (node (ref "C117") (pin "2") (pinfunction "2_2") (pintype "passive"))
      (node (ref "C118") (pin "1") (pinfunction "1_1") (pintype "passive"))
      (node (ref "D33") (pin "1") (pinfunction "K_1") (pintype "passive"))
      (node (ref "U20") (pin "2") (pinfunction "IN_2") (pintype "input"))
    )
    (net (code "6") (name "-5.0V_PH") (class "Default")
      (node (ref "C71") (pin "1") (pinfunction "1_1") (pintype "passive"))
      (node (ref "C72") (pin "2") (pinfunction "2_2") (pintype "passive"))
      (node (ref "D22") (pin "2") (pinfunction "A_2") (pintype "passive"))
      (node (ref "FB13") (pin "2") (pinfunction "2_2") (pintype "passive"))
      (node (ref "R57") (pin "2") (pinfunction "2_2") (pintype "passive"))
      (node (ref "TP16") (pin "1") (pinfunction "1_1") (pintype "passive"))
    )
    (net (code "7") (name "-5.0V_WSH") (class "Default")
      (node (ref "C106") (pin "1") (pinfunction "1_1") (pintype "passive"))
      (node (ref "C110") (pin "2") (pinfunction "2_2") (pintype "passive"))
      (node (ref "D31") (pin "2") (pinfunction "A_2") (pintype "passive"))
      (node (ref "FB17") (pin "2") (pinfunction "2_2") (pintype "passive"))
      (node (ref "R33") (pin "2") (pinfunction "2_2") (pintype "passive"))
      (node (ref "TP10") (pin "1") (pinfunction "1_1") (pintype "passive"))
    )
    (net (code "8") (name "-6V_PH") (class "Default")
      (node (ref "C73") (pin "2") (pinfunction "2_2") (pintype "passive"))
      (node (ref "C75") (pin "2") (pinfunction "2_2") (pintype "passive"))
      (node (ref "C78") (pin "1") (pinfunction "1_1") (pintype "passive"))
      (node (ref "C81") (pin "2") (pinfunction "2_2") (pintype "passive"))
      (node (ref "D21") (pin "2") (pinfunction "A_2") (pintype "passive"))
      (node (ref "U15") (pin "5") (pinfunction "EN_5") (pintype "input"))
      (node (ref "U15") (pin "8") (pinfunction "VIN_8") (pintype "power_in"))
    )
    (net (code "9") (name "-6V_WSH") (class "Default")
      (node (ref "C108") (pin "2") (pinfunction "2_2") (pintype "passive"))
      (node (ref "C109") (pin "2") (pinfunction "2_2") (pintype "passive"))
      (node (ref "C114") (pin "1") (pinfunction "1_1") (pintype "passive"))
      (node (ref "C116") (pin "2") (pinfunction "2_2") (pintype "passive"))
      (node (ref "D32") (pin "2") (pinfunction "A_2") (pintype "passive"))
      (node (ref "U19") (pin "5") (pinfunction "EN_5") (pintype "input"))
      (node (ref "U19") (pin "8") (pinfunction "VIN_8") (pintype "power_in"))
    )
    (net (code "10") (name "DGND") (class "Default")
      (node (ref "C23") (pin "1") (pinfunction "1_1") (pintype "passive"))
      (node (ref "C25") (pin "1") (pinfunction "1_1") (pintype "passive"))
      (node (ref "C26") (pin "1") (pinfunction "1_1") (pintype "passive"))
      (node (ref "C28") (pin "2") (pinfunction "-_2") (pintype "passive"))
      (node (ref "C49") (pin "1") (pinfunction "1_1") (pintype "passive"))
      (node (ref "C50") (pin "1") (pinfunction "1_1") (pintype "passive"))
      (node (ref "C51") (pin "1") (pinfunction "1_1") (pintype "passive"))
      (node (ref "U10") (pin "4") (pinfunction "GND_4") (pintype "power_in"))
      (node (ref "U10") (pin "5") (pinfunction "GND_5") (pintype "power_in"))
      (node (ref "U6") (pin "4") (pinfunction "GND_4") (pintype "power_in"))
      (node (ref "U6") (pin "5") (pinfunction "GND_5") (pintype "power_in"))
    )
    (net (code "11") (name "GND_PH") (class "Default")
      (node (ref "C51") (pin "2") (pinfunction "2_2") (pintype "passive"))
      (node (ref "C71") (pin "2") (pinfunction "2_2") (pintype "passive"))
      (node (ref "C72") (pin "1") (pinfunction "1_1") (pintype "passive"))
      (node (ref "C73") (pin "1") (pinfunction "1_1") (pintype "passive"))
      (node (ref "C74") (pin "1") (pinfunction "1_1") (pintype "passive"))
      (node (ref "C75") (pin "1") (pinfunction "1_1") (pintype "passive"))
      (node (ref "C77") (pin "2") (pinfunction "2_2") (pintype "passive"))
      (node (ref "C78") (pin "2") (pinfunction "2_2") (pintype "passive"))
      (node (ref "C79") (pin "1") (pinfunction "1_1") (pintype "passive"))
      (node (ref "C80") (pin "2") (pinfunction "2_2") (pintype "passive"))
      (node (ref "C81") (pin "1") (pinfunction "1_1") (pintype "passive"))
      (node (ref "C82") (pin "1") (pinfunction "1_1") (pintype "passive"))
      (node (ref "C83") (pin "2") (pinfunction "2_2") (pintype "passive"))
      (node (ref "C84") (pin "1") (pinfunction "1_1") (pintype "passive"))
      (node (ref "C85") (pin "2") (pinfunction "2_2") (pintype "passive"))
      (node (ref "C86") (pin "1") (pinfunction "1_1") (pintype "passive"))
      (node (ref "D11") (pin "2") (pinfunction "A_2") (pintype "passive"))
      (node (ref "D22") (pin "1") (pinfunction "K_1") (pintype "passive"))
      (node (ref "D24") (pin "2") (pinfunction "A_2") (pintype "passive"))
      (node (ref "D9") (pin "1") (pinfunction "C_1") (pintype "passive"))
      (node (ref "R94") (pin "1") (pinfunction "1_1") (pintype "passive"))
      (node (ref "T5") (pin "4") (pinfunction "4_4") (pintype "passive"))
      (node (ref "U15") (pin "3") (pinfunction "NC_3") (pintype "passive"))
      (node (ref "U15") (pin "4") (pinfunction "GND_4") (pintype "power_in"))
      (node (ref "U15") (pin "9") (pinfunction "TPAD_9") (pintype "passive"))
      (node (ref "U16") (pin "1") (pinfunction "GND_1") (pintype "power_in"))
    )
    (net (code "12") (name "GND_WSH") (class "Default")
      (node (ref "C106") (pin "2") (pinfunction "2_2") (pintype "passive"))
      (node (ref "C107") (pin "1") (pinfunction "1_1") (pintype "passive"))
      (node (ref "C108") (pin "1") (pinfunction "1_1") (pintype "passive"))
      (node (ref "C109") (pin "1") (pinfunction "1_1") (pintype "passive"))
      (node (ref "C110") (pin "1") (pinfunction "1_1") (pintype "passive"))
      (node (ref "C112") (pin "2") (pinfunction "2_2") (pintype "passive"))
      (node (ref "C113") (pin "2") (pinfunction "2_2") (pintype "passive"))
      (node (ref "C114") (pin "2") (pinfunction "2_2") (pintype "passive"))
      (node (ref "C115") (pin "1") (pinfunction "1_1") (pintype "passive"))
      (node (ref "C116") (pin "1") (pinfunction "1_1") (pintype "passive"))
      (node (ref "C117") (pin "1") (pinfunction "1_1") (pintype "passive"))
      (node (ref "C118") (pin "2") (pinfunction "2_2") (pintype "passive"))
      (node (ref "C119") (pin "1") (pinfunction "1_1") (pintype "passive"))
      (node (ref "C120") (pin "2") (pinfunction "2_2") (pintype "passive"))
      (node (ref "C121") (pin "1") (pinfunction "1_1") (pintype "passive"))
      (node (ref "C26") (pin "2") (pinfunction "2_2") (pintype "passive"))
      (node (ref "D31") (pin "1") (pinfunction "K_1") (pintype "passive"))
      (node (ref "D34") (pin "2") (pinfunction "A_2") (pintype "passive"))
      (node (ref "D5") (pin "1") (pinfunction "C_1") (pintype "passive"))
      (node (ref "D6") (pin "2") (pinfunction "A_2") (pintype "passive"))
      (node (ref "R99") (pin "1") (pinfunction "1_1") (pintype "passive"))
      (node (ref "T3") (pin "4") (pinfunction "4_4") (pintype "passive"))
      (node (ref "U19") (pin "3") (pinfunction "NC_3") (pintype "passive"))
      (node (ref "U19") (pin "4") (pinfunction "GND_4") (pintype "power_in"))
      (node (ref "U19") (pin "9") (pinfunction "TPAD_9") (pintype "passive"))
      (node (ref "U20") (pin "1") (pinfunction "GND_1") (pintype "power_in"))
    )
    (net (code "13") (name "Net-(D5-A)") (class "Default")
      (node (ref "D5") (pin "2") (pinfunction "A_2") (pintype "passive"))
      (node (ref "R21") (pin "1") (pinfunction "1_1") (pintype "passive"))
    )
    (net (code "14") (name "Net-(D6-C)") (class "Default")
      (node (ref "D6") (pin "1") (pinfunction "C_1") (pintype "passive"))
      (node (ref "R33") (pin "1") (pinfunction "1_1") (pintype "passive"))
    )
    (net (code "15") (name "Net-(D9-A)") (class "Default")
      (node (ref "D9") (pin "2") (pinfunction "A_2") (pintype "passive"))
      (node (ref "R55") (pin "1") (pinfunction "1_1") (pintype "passive"))
    )
    (net (code "16") (name "Net-(D11-C)") (class "Default")
      (node (ref "D11") (pin "1") (pinfunction "C_1") (pintype "passive"))
      (node (ref "R57") (pin "1") (pinfunction "1_1") (pintype "passive"))
    )
    (net (code "17") (name "Net-(D21-K)") (class "Default")
      (node (ref "D21") (pin "1") (pinfunction "K_1") (pintype "passive"))
      (node (ref "D23") (pin "2") (pinfunction "A_2") (pintype "passive"))
      (node (ref "T5") (pin "6") (pinfunction "6_6") (pintype "passive"))
    )
    (net (code "18") (name "Net-(D32-K)") (class "Default")
      (node (ref "D32") (pin "1") (pinfunction "K_1") (pintype "passive"))
      (node (ref "D33") (pin "2") (pinfunction "A_2") (pintype "passive"))
      (node (ref "T3") (pin "6") (pinfunction "6_6") (pintype "passive"))
    )
    (net (code "19") (name "Net-(U6-D1)") (class "Default")
      (node (ref "T3") (pin "3") (pinfunction "3_3") (pintype "passive"))
      (node (ref "U6") (pin "1") (pinfunction "D1_1") (pintype "output"))
    )
    (net (code "20") (name "Net-(U6-D2)") (class "Default")
      (node (ref "T3") (pin "1") (pinfunction "1_1") (pintype "passive"))
      (node (ref "U6") (pin "3") (pinfunction "D2_3") (pintype "output"))
    )
    (net (code "21") (name "Net-(U10-D1)") (class "Default")
      (node (ref "T5") (pin "3") (pinfunction "3_3") (pintype "passive"))
      (node (ref "U10") (pin "1") (pinfunction "D1_1") (pintype "output"))
    )
    (net (code "22") (name "Net-(U10-D2)") (class "Default")
      (node (ref "T5") (pin "1") (pinfunction "1_1") (pintype "passive"))
      (node (ref "U10") (pin "3") (pinfunction "D2_3") (pintype "output"))
    )
    (net (code "23") (name "Net-(U15-FB)") (class "Default")
      (node (ref "C76") (pin "2") (pinfunction "2_2") (pintype "passive"))
      (node (ref "R94") (pin "2") (pinfunction "2_2") (pintype "passive"))
      (node (ref "R95") (pin "1") (pinfunction "1_1") (pintype "passive"))
      (node (ref "U15") (pin "2") (pinfunction "FB_2") (pintype "input"))
    )
    (net (code "24") (name "Net-(U15-NR{slash}SS)") (class "Default")
      (node (ref "C74") (pin "2") (pinfunction "2_2") (pintype "passive"))
      (node (ref "U15") (pin "6") (pinfunction "NR/SS_6") (pintype "input"))
    )
    (net (code "25") (name "Net-(U15-OUT)") (class "Default")
      (node (ref "C76") (pin "1") (pinfunction "1_1") (pintype "passive"))
      (node (ref "C79") (pin "2") (pinfunction "2_2") (pintype "passive"))
      (node (ref "FB13") (pin "1") (pinfunction "1_1") (pintype "passive"))
      (node (ref "R95") (pin "2") (pinfunction "2_2") (pintype "passive"))
      (node (ref "U15") (pin "1") (pinfunction "OUT_1") (pintype "power_in"))
    )
    (net (code "26") (name "Net-(U16-OUT)") (class "Default")
      (node (ref "C86") (pin "2") (pinfunction "2_2") (pintype "passive"))
      (node (ref "FB14") (pin "1") (pinfunction "1_1") (pintype "passive"))
      (node (ref "U16") (pin "3") (pinfunction "OUT_3") (pintype "output"))
    )
    (net (code "27") (name "Net-(U19-FB)") (class "Default")
      (node (ref "C111") (pin "1") (pinfunction "1_1") (pintype "passive"))
      (node (ref "R100") (pin "1") (pinfunction "1_1") (pintype "passive"))
      (node (ref "R99") (pin "2") (pinfunction "2_2") (pintype "passive"))
      (node (ref "U19") (pin "2") (pinfunction "FB_2") (pintype "input"))
    )
    (net (code "28") (name "Net-(U19-NR{slash}SS)") (class "Default")
      (node (ref "C107") (pin "2") (pinfunction "2_2") (pintype "passive"))
      (node (ref "U19") (pin "6") (pinfunction "NR/SS_6") (pintype "input"))
    )
    (net (code "29") (name "Net-(U19-OUT)") (class "Default")
      (node (ref "C111") (pin "2") (pinfunction "2_2") (pintype "passive"))
      (node (ref "C115") (pin "2") (pinfunction "2_2") (pintype "passive"))
      (node (ref "FB17") (pin "1") (pinfunction "1_1") (pintype "passive"))
      (node (ref "R100") (pin "2") (pinfunction "2_2") (pintype "passive"))
      (node (ref "U19") (pin "1") (pinfunction "OUT_1") (pintype "power_in"))
    )
    (net (code "30") (name "Net-(U20-OUT)") (class "Default")
      (node (ref "C121") (pin "2") (pinfunction "2_2") (pintype "passive"))
      (node (ref "FB18") (pin "1") (pinfunction "1_1") (pintype "passive"))
      (node (ref "U20") (pin "3") (pinfunction "OUT_3") (pintype "output"))
    )
    (net (code "31") (name "unconnected-(T3-Pad5)") (class "Default")
      (node (ref "T3") (pin "5") (pinfunction "5_5") (pintype "passive"))
    )
    (net (code "32") (name "unconnected-(T5-Pad5)") (class "Default")
      (node (ref "T5") (pin "5") (pinfunction "5_5") (pintype "passive"))
    )
    (net (code "33") (name "unconnected-(U15-DNC-Pad7)") (class "Default")
      (node (ref "U15") (pin "7") (pinfunction "DNC_7") (pintype "passive"))
    )
    (net (code "34") (name "unconnected-(U16-NC-Pad4)") (class "Default")
      (node (ref "U16") (pin "4") (pinfunction "NC_4") (pintype "power_in"))
    )
    (net (code "35") (name "unconnected-(U16-NC-Pad5)") (class "Default")
      (node (ref "U16") (pin "5") (pinfunction "NC_5") (pintype "power_in"))
    )
    (net (code "36") (name "unconnected-(U19-DNC-Pad7)") (class "Default")
      (node (ref "U19") (pin "7") (pinfunction "DNC_7") (pintype "passive"))
    )
    (net (code "37") (name "unconnected-(U20-NC-Pad4)") (class "Default")
      (node (ref "U20") (pin "4") (pinfunction "NC_4") (pintype "power_in"))
    )
    (net (code "38") (name "unconnected-(U20-NC-Pad5)") (class "Default")
      (node (ref "U20") (pin "5") (pinfunction "NC_5") (pintype "power_in"))
    )
  )
)
